# Battery_Display_Board.net
KiCad netlist of a schematic drawn in EAGLE
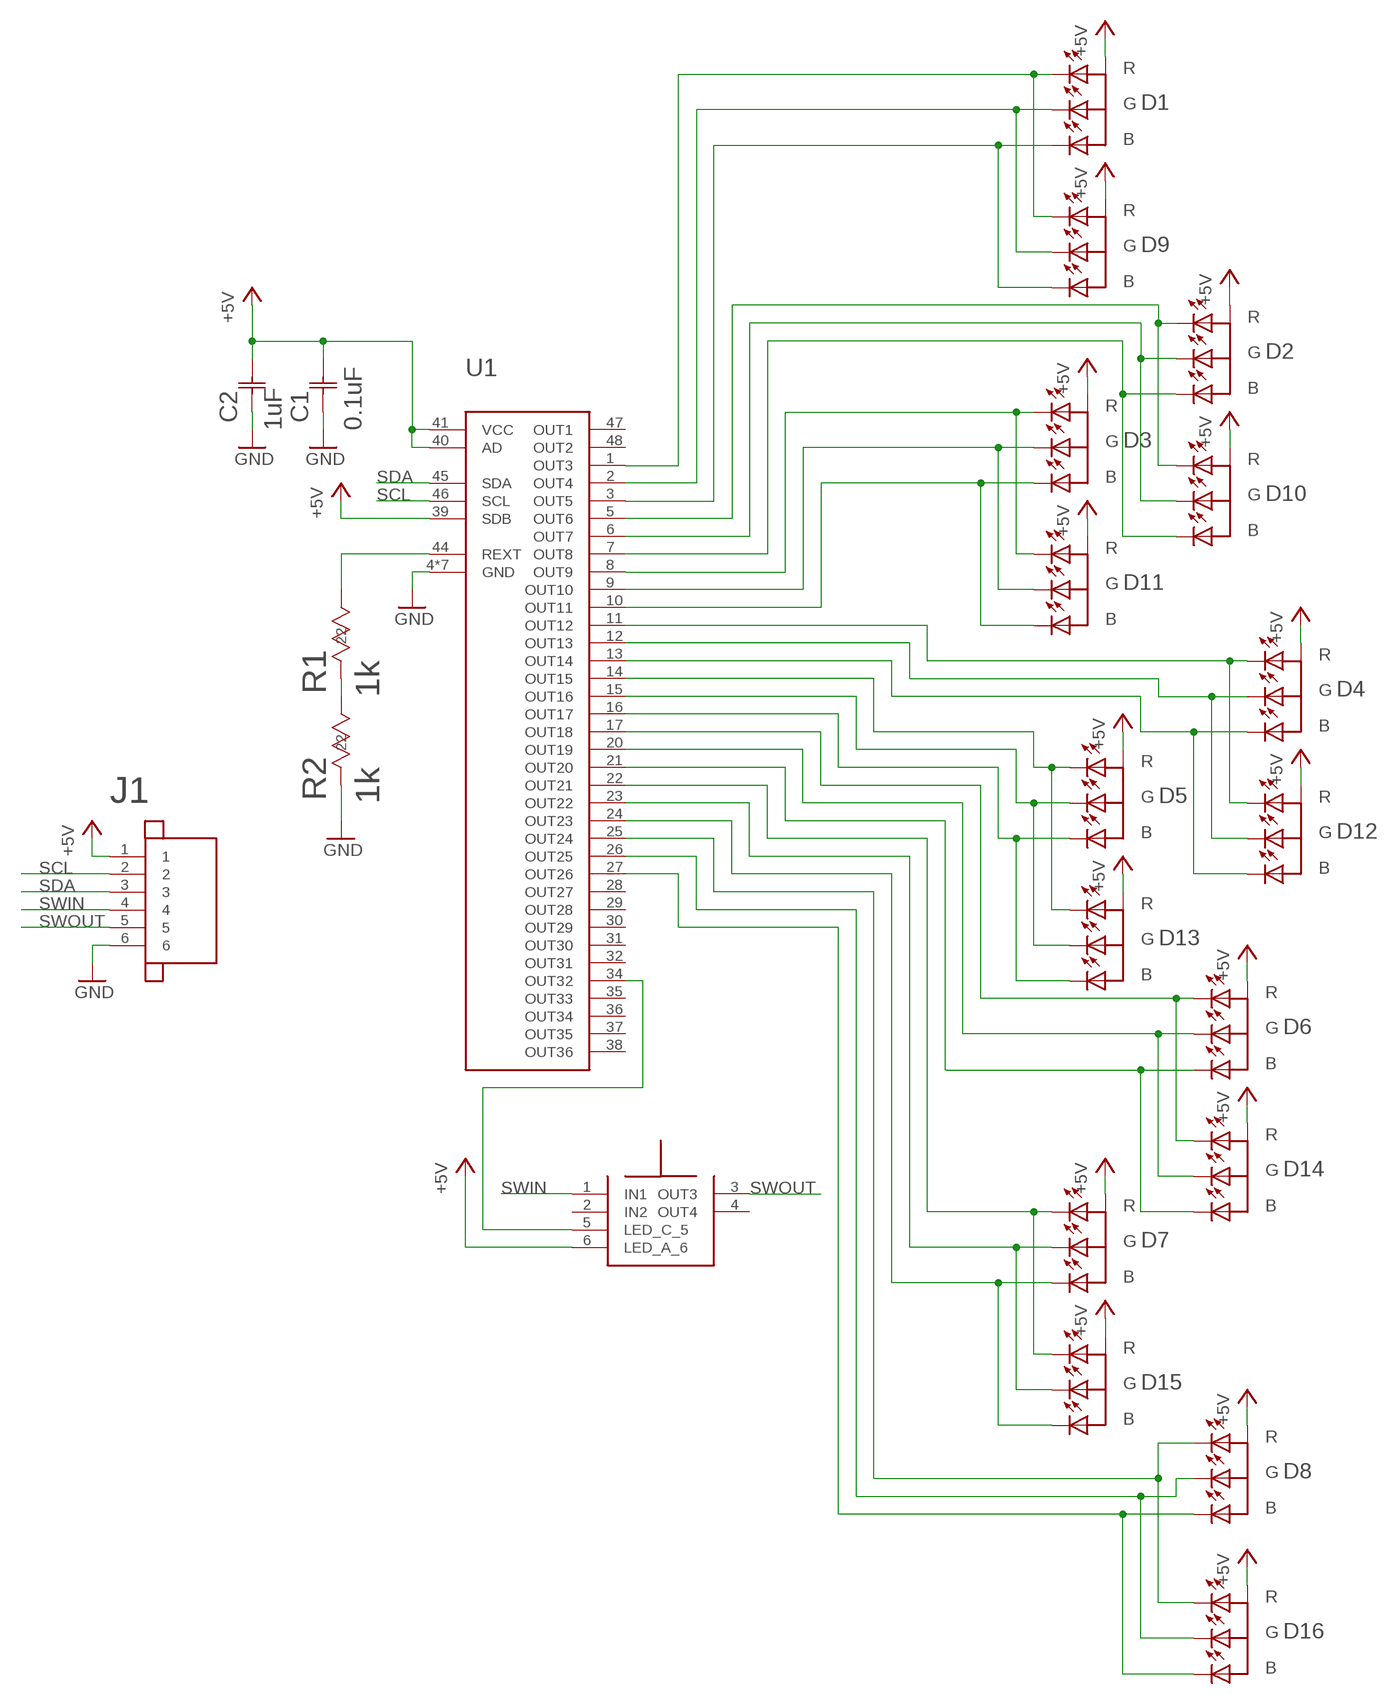
[diagram p0: schematic, sheet 1]

(export (version "E")
  (design (tool "Eeschema 10.0.6"))
  (components
    (comp (ref "C1")
      (value "0.1uF")
      (footprint "eagle-import:0805")
      (fields
        (field (name "MANUFACTURER_PART_NUMBER") "08055C104KAT2A")
        (field (name "COPYRIGHT") "Copyright C 2015 Accelerated Designs. All rights reserved")
      )
      (libsource (lib "eagle-import") (part "08055C104KAT2A"))
    )
    (comp (ref "C2")
      (value "1uF")
      (footprint "eagle-import:YAG_CC0805")
      (fields
        (field (name "MANUFACTURER_PART_NUMBER") "CC0805KKX7R7BB105")
        (field (name "COPYRIGHT") "Copyright C 2015 Accelerated Designs. All rights reserved")
      )
      (libsource (lib "eagle-import") (part "CC0805KKX7R7BB105"))
    )
    (comp (ref "D1")
      (value "ASMB-MTB0-0A3A2")
      (footprint "eagle-import:ASMB-MTB0_LED")
      (libsource (lib "eagle-import") (part "ASMB-MTB0-0A3A2"))
    )
    (comp (ref "D2")
      (value "ASMB-MTB0-0A3A2")
      (footprint "eagle-import:ASMB-MTB0_LED")
      (libsource (lib "eagle-import") (part "ASMB-MTB0-0A3A2"))
    )
    (comp (ref "D3")
      (value "ASMB-MTB0-0A3A2")
      (footprint "eagle-import:ASMB-MTB0_LED")
      (libsource (lib "eagle-import") (part "ASMB-MTB0-0A3A2"))
    )
    (comp (ref "D4")
      (value "ASMB-MTB0-0A3A2")
      (footprint "eagle-import:ASMB-MTB0_LED")
      (libsource (lib "eagle-import") (part "ASMB-MTB0-0A3A2"))
    )
    (comp (ref "D5")
      (value "ASMB-MTB0-0A3A2")
      (footprint "eagle-import:ASMB-MTB0_LED")
      (libsource (lib "eagle-import") (part "ASMB-MTB0-0A3A2"))
    )
    (comp (ref "D6")
      (value "ASMB-MTB0-0A3A2")
      (footprint "eagle-import:ASMB-MTB0_LED")
      (libsource (lib "eagle-import") (part "ASMB-MTB0-0A3A2"))
    )
    (comp (ref "D7")
      (value "ASMB-MTB0-0A3A2")
      (footprint "eagle-import:ASMB-MTB0_LED")
      (libsource (lib "eagle-import") (part "ASMB-MTB0-0A3A2"))
    )
    (comp (ref "D8")
      (value "ASMB-MTB0-0A3A2")
      (footprint "eagle-import:ASMB-MTB0_LED")
      (libsource (lib "eagle-import") (part "ASMB-MTB0-0A3A2"))
    )
    (comp (ref "D9")
      (value "ASMB-MTB0-0A3A2")
      (footprint "eagle-import:ASMB-MTB0_LED")
      (libsource (lib "eagle-import") (part "ASMB-MTB0-0A3A2"))
    )
    (comp (ref "D10")
      (value "ASMB-MTB0-0A3A2")
      (footprint "eagle-import:ASMB-MTB0_LED")
      (libsource (lib "eagle-import") (part "ASMB-MTB0-0A3A2"))
    )
    (comp (ref "D11")
      (value "ASMB-MTB0-0A3A2")
      (footprint "eagle-import:ASMB-MTB0_LED")
      (libsource (lib "eagle-import") (part "ASMB-MTB0-0A3A2"))
    )
    (comp (ref "D12")
      (value "ASMB-MTB0-0A3A2")
      (footprint "eagle-import:ASMB-MTB0_LED")
      (libsource (lib "eagle-import") (part "ASMB-MTB0-0A3A2"))
    )
    (comp (ref "D13")
      (value "ASMB-MTB0-0A3A2")
      (footprint "eagle-import:ASMB-MTB0_LED")
      (libsource (lib "eagle-import") (part "ASMB-MTB0-0A3A2"))
    )
    (comp (ref "D14")
      (value "ASMB-MTB0-0A3A2")
      (footprint "eagle-import:ASMB-MTB0_LED")
      (libsource (lib "eagle-import") (part "ASMB-MTB0-0A3A2"))
    )
    (comp (ref "D15")
      (value "ASMB-MTB0-0A3A2")
      (footprint "eagle-import:ASMB-MTB0_LED")
      (libsource (lib "eagle-import") (part "ASMB-MTB0-0A3A2"))
    )
    (comp (ref "D16")
      (value "ASMB-MTB0-0A3A2")
      (footprint "eagle-import:ASMB-MTB0_LED")
      (libsource (lib "eagle-import") (part "ASMB-MTB0-0A3A2"))
    )
    (comp (ref "J1")
      (value "JST_SH_6POS_SIDE")
      (footprint "eagle-import:JST_SH_6POS_SIDE")
      (libsource (lib "eagle-import") (part "JST_SH_6POS_SIDE"))
    )
    (comp (ref "R1")
      (value "1k")
      (footprint "eagle-import:RC0603N-M")
      (fields
        (field (name "DIGIKEYPARTNUMBER") "3111.0KGRTRND")
        (field (name "MANUFACTURER_PART_NUMBER") "RC0603JR071KL")
        (field (name "NEWARKPARTNUMBER") "14M7231")
        (field (name "COPYRIGHT") "Copyright C 2015 Accelerated Designs. All rights reserved")
      )
      (libsource (lib "eagle-import") (part "RC0603JR-071KLRC0603N-M"))
    )
    (comp (ref "R2")
      (value "1k")
      (footprint "eagle-import:RC0603N-M")
      (fields
        (field (name "DIGIKEYPARTNUMBER") "3111.0KGRTRND")
        (field (name "MANUFACTURER_PART_NUMBER") "RC0603JR071KL")
        (field (name "NEWARKPARTNUMBER") "14M7231")
        (field (name "COPYRIGHT") "Copyright C 2015 Accelerated Designs. All rights reserved")
      )
      (libsource (lib "eagle-import") (part "RC0603JR-071KLRC0603N-M"))
    )
    (comp (ref "U$2")
      (value "LED_TACT_SWITCH")
      (footprint "eagle-import:LED_TACT_SWITCH")
      (libsource (lib "eagle-import") (part "LED_TACT_SWITCH"))
    )
    (comp (ref "U1")
      (value "IS31FL3236")
      (footprint "eagle-import:TQFP-48")
      (libsource (lib "eagle-import") (part "IS31FL3236"))
    )
  )
  (nets
    (net (code "1") (name "+5V") (class "Default")
      (node (ref "C1") (pin "2") (pinfunction "2_2") (pintype "passive"))
      (node (ref "C2") (pin "2") (pinfunction "22_2") (pintype "passive"))
      (node (ref "D1") (pin "1") (pinfunction "A_1") (pintype "passive"))
      (node (ref "D10") (pin "1") (pinfunction "A_1") (pintype "passive"))
      (node (ref "D11") (pin "1") (pinfunction "A_1") (pintype "passive"))
      (node (ref "D12") (pin "1") (pinfunction "A_1") (pintype "passive"))
      (node (ref "D13") (pin "1") (pinfunction "A_1") (pintype "passive"))
      (node (ref "D14") (pin "1") (pinfunction "A_1") (pintype "passive"))
      (node (ref "D15") (pin "1") (pinfunction "A_1") (pintype "passive"))
      (node (ref "D16") (pin "1") (pinfunction "A_1") (pintype "passive"))
      (node (ref "D2") (pin "1") (pinfunction "A_1") (pintype "passive"))
      (node (ref "D3") (pin "1") (pinfunction "A_1") (pintype "passive"))
      (node (ref "D4") (pin "1") (pinfunction "A_1") (pintype "passive"))
      (node (ref "D5") (pin "1") (pinfunction "A_1") (pintype "passive"))
      (node (ref "D6") (pin "1") (pinfunction "A_1") (pintype "passive"))
      (node (ref "D7") (pin "1") (pinfunction "A_1") (pintype "passive"))
      (node (ref "D8") (pin "1") (pinfunction "A_1") (pintype "passive"))
      (node (ref "D9") (pin "1") (pinfunction "A_1") (pintype "passive"))
      (node (ref "J1") (pin "1") (pinfunction "1_1") (pintype "bidirectional"))
      (node (ref "U$2") (pin "6") (pinfunction "LED_A_6_6") (pintype "bidirectional"))
      (node (ref "U1") (pin "39") (pinfunction "SDB_39") (pintype "bidirectional"))
      (node (ref "U1") (pin "40") (pinfunction "AD_40") (pintype "bidirectional"))
      (node (ref "U1") (pin "41") (pinfunction "VCC_41") (pintype "bidirectional"))
    )
    (net (code "2") (name "/SCL") (class "Default")
      (node (ref "J1") (pin "2") (pinfunction "2_2") (pintype "bidirectional"))
      (node (ref "U1") (pin "46") (pinfunction "SCL_46") (pintype "bidirectional"))
    )
    (net (code "3") (name "/SDA") (class "Default")
      (node (ref "J1") (pin "3") (pinfunction "3_3") (pintype "bidirectional"))
      (node (ref "U1") (pin "45") (pinfunction "SDA_45") (pintype "bidirectional"))
    )
    (net (code "4") (name "/SWIN") (class "Default")
      (node (ref "J1") (pin "4") (pinfunction "4_4") (pintype "bidirectional"))
      (node (ref "U$2") (pin "1") (pinfunction "IN1_1") (pintype "bidirectional"))
    )
    (net (code "5") (name "/SWOUT") (class "Default")
      (node (ref "J1") (pin "5") (pinfunction "5_5") (pintype "bidirectional"))
      (node (ref "U$2") (pin "3") (pinfunction "OUT3_3") (pintype "bidirectional"))
    )
    (net (code "6") (name "GND") (class "Default")
      (node (ref "C1") (pin "1") (pinfunction "1_1") (pintype "passive"))
      (node (ref "C2") (pin "1") (pinfunction "11_1") (pintype "passive"))
      (node (ref "J1") (pin "6") (pinfunction "6_6") (pintype "bidirectional"))
      (node (ref "R2") (pin "2") (pinfunction "22_2") (pintype "passive"))
      (node (ref "U1") (pin "18") (pinfunction "GND_18") (pintype "bidirectional"))
      (node (ref "U1") (pin "19") (pinfunction "GND_19") (pintype "bidirectional"))
      (node (ref "U1") (pin "33") (pinfunction "GND_33") (pintype "bidirectional"))
      (node (ref "U1") (pin "4") (pinfunction "GND_4") (pintype "bidirectional"))
      (node (ref "U1") (pin "42") (pinfunction "GND_42") (pintype "bidirectional"))
      (node (ref "U1") (pin "43") (pinfunction "GND_43") (pintype "bidirectional"))
      (node (ref "U1") (pin "EP") (pinfunction "GND_EP") (pintype "bidirectional"))
    )
    (net (code "7") (name "Net-(D1-B)") (class "Default")
      (node (ref "D1") (pin "2") (pinfunction "B_2") (pintype "passive"))
      (node (ref "D9") (pin "2") (pinfunction "B_2") (pintype "passive"))
      (node (ref "U1") (pin "3") (pinfunction "OUT5_3") (pintype "bidirectional"))
    )
    (net (code "8") (name "Net-(D1-G)") (class "Default")
      (node (ref "D1") (pin "3") (pinfunction "G_3") (pintype "passive"))
      (node (ref "D9") (pin "3") (pinfunction "G_3") (pintype "passive"))
      (node (ref "U1") (pin "2") (pinfunction "OUT4_2") (pintype "bidirectional"))
    )
    (net (code "9") (name "Net-(D1-R)") (class "Default")
      (node (ref "D1") (pin "4") (pinfunction "R_4") (pintype "passive"))
      (node (ref "D9") (pin "4") (pinfunction "R_4") (pintype "passive"))
      (node (ref "U1") (pin "1") (pinfunction "OUT3_1") (pintype "bidirectional"))
    )
    (net (code "10") (name "Net-(D10-B)") (class "Default")
      (node (ref "D10") (pin "2") (pinfunction "B_2") (pintype "passive"))
      (node (ref "D2") (pin "2") (pinfunction "B_2") (pintype "passive"))
      (node (ref "U1") (pin "7") (pinfunction "OUT8_7") (pintype "bidirectional"))
    )
    (net (code "11") (name "Net-(D10-G)") (class "Default")
      (node (ref "D10") (pin "3") (pinfunction "G_3") (pintype "passive"))
      (node (ref "D2") (pin "3") (pinfunction "G_3") (pintype "passive"))
      (node (ref "U1") (pin "6") (pinfunction "OUT7_6") (pintype "bidirectional"))
    )
    (net (code "12") (name "Net-(D10-R)") (class "Default")
      (node (ref "D10") (pin "4") (pinfunction "R_4") (pintype "passive"))
      (node (ref "D2") (pin "4") (pinfunction "R_4") (pintype "passive"))
      (node (ref "U1") (pin "5") (pinfunction "OUT6_5") (pintype "bidirectional"))
    )
    (net (code "13") (name "Net-(D11-B)") (class "Default")
      (node (ref "D11") (pin "2") (pinfunction "B_2") (pintype "passive"))
      (node (ref "D3") (pin "2") (pinfunction "B_2") (pintype "passive"))
      (node (ref "U1") (pin "10") (pinfunction "OUT11_10") (pintype "bidirectional"))
    )
    (net (code "14") (name "Net-(D11-G)") (class "Default")
      (node (ref "D11") (pin "3") (pinfunction "G_3") (pintype "passive"))
      (node (ref "D3") (pin "3") (pinfunction "G_3") (pintype "passive"))
      (node (ref "U1") (pin "9") (pinfunction "OUT10_9") (pintype "bidirectional"))
    )
    (net (code "15") (name "Net-(D11-R)") (class "Default")
      (node (ref "D11") (pin "4") (pinfunction "R_4") (pintype "passive"))
      (node (ref "D3") (pin "4") (pinfunction "R_4") (pintype "passive"))
      (node (ref "U1") (pin "8") (pinfunction "OUT9_8") (pintype "bidirectional"))
    )
    (net (code "16") (name "Net-(D12-B)") (class "Default")
      (node (ref "D12") (pin "2") (pinfunction "B_2") (pintype "passive"))
      (node (ref "D4") (pin "2") (pinfunction "B_2") (pintype "passive"))
      (node (ref "U1") (pin "13") (pinfunction "OUT14_13") (pintype "bidirectional"))
    )
    (net (code "17") (name "Net-(D12-G)") (class "Default")
      (node (ref "D12") (pin "3") (pinfunction "G_3") (pintype "passive"))
      (node (ref "D4") (pin "3") (pinfunction "G_3") (pintype "passive"))
      (node (ref "U1") (pin "12") (pinfunction "OUT13_12") (pintype "bidirectional"))
    )
    (net (code "18") (name "Net-(D12-R)") (class "Default")
      (node (ref "D12") (pin "4") (pinfunction "R_4") (pintype "passive"))
      (node (ref "D4") (pin "4") (pinfunction "R_4") (pintype "passive"))
      (node (ref "U1") (pin "11") (pinfunction "OUT12_11") (pintype "bidirectional"))
    )
    (net (code "19") (name "Net-(D13-B)") (class "Default")
      (node (ref "D13") (pin "2") (pinfunction "B_2") (pintype "passive"))
      (node (ref "D5") (pin "2") (pinfunction "B_2") (pintype "passive"))
      (node (ref "U1") (pin "16") (pinfunction "OUT17_16") (pintype "bidirectional"))
    )
    (net (code "20") (name "Net-(D13-G)") (class "Default")
      (node (ref "D13") (pin "3") (pinfunction "G_3") (pintype "passive"))
      (node (ref "D5") (pin "3") (pinfunction "G_3") (pintype "passive"))
      (node (ref "U1") (pin "15") (pinfunction "OUT16_15") (pintype "bidirectional"))
    )
    (net (code "21") (name "Net-(D13-R)") (class "Default")
      (node (ref "D13") (pin "4") (pinfunction "R_4") (pintype "passive"))
      (node (ref "D5") (pin "4") (pinfunction "R_4") (pintype "passive"))
      (node (ref "U1") (pin "14") (pinfunction "OUT15_14") (pintype "bidirectional"))
    )
    (net (code "22") (name "Net-(D14-B)") (class "Default")
      (node (ref "D14") (pin "2") (pinfunction "B_2") (pintype "passive"))
      (node (ref "D6") (pin "2") (pinfunction "B_2") (pintype "passive"))
      (node (ref "U1") (pin "21") (pinfunction "OUT20_21") (pintype "bidirectional"))
    )
    (net (code "23") (name "Net-(D14-G)") (class "Default")
      (node (ref "D14") (pin "3") (pinfunction "G_3") (pintype "passive"))
      (node (ref "D6") (pin "3") (pinfunction "G_3") (pintype "passive"))
      (node (ref "U1") (pin "20") (pinfunction "OUT19_20") (pintype "bidirectional"))
    )
    (net (code "24") (name "Net-(D14-R)") (class "Default")
      (node (ref "D14") (pin "4") (pinfunction "R_4") (pintype "passive"))
      (node (ref "D6") (pin "4") (pinfunction "R_4") (pintype "passive"))
      (node (ref "U1") (pin "17") (pinfunction "OUT18_17") (pintype "bidirectional"))
    )
    (net (code "25") (name "Net-(D15-B)") (class "Default")
      (node (ref "D15") (pin "2") (pinfunction "B_2") (pintype "passive"))
      (node (ref "D7") (pin "2") (pinfunction "B_2") (pintype "passive"))
      (node (ref "U1") (pin "24") (pinfunction "OUT23_24") (pintype "bidirectional"))
    )
    (net (code "26") (name "Net-(D15-G)") (class "Default")
      (node (ref "D15") (pin "3") (pinfunction "G_3") (pintype "passive"))
      (node (ref "D7") (pin "3") (pinfunction "G_3") (pintype "passive"))
      (node (ref "U1") (pin "23") (pinfunction "OUT22_23") (pintype "bidirectional"))
    )
    (net (code "27") (name "Net-(D15-R)") (class "Default")
      (node (ref "D15") (pin "4") (pinfunction "R_4") (pintype "passive"))
      (node (ref "D7") (pin "4") (pinfunction "R_4") (pintype "passive"))
      (node (ref "U1") (pin "22") (pinfunction "OUT21_22") (pintype "bidirectional"))
    )
    (net (code "28") (name "Net-(D16-B)") (class "Default")
      (node (ref "D16") (pin "2") (pinfunction "B_2") (pintype "passive"))
      (node (ref "D8") (pin "2") (pinfunction "B_2") (pintype "passive"))
      (node (ref "U1") (pin "27") (pinfunction "OUT26_27") (pintype "bidirectional"))
    )
    (net (code "29") (name "Net-(D16-G)") (class "Default")
      (node (ref "D16") (pin "3") (pinfunction "G_3") (pintype "passive"))
      (node (ref "D8") (pin "3") (pinfunction "G_3") (pintype "passive"))
      (node (ref "U1") (pin "26") (pinfunction "OUT25_26") (pintype "bidirectional"))
    )
    (net (code "30") (name "Net-(D16-R)") (class "Default")
      (node (ref "D16") (pin "4") (pinfunction "R_4") (pintype "passive"))
      (node (ref "D8") (pin "4") (pinfunction "R_4") (pintype "passive"))
      (node (ref "U1") (pin "25") (pinfunction "OUT24_25") (pintype "bidirectional"))
    )
    (net (code "31") (name "Net-(R1-11)") (class "Default")
      (node (ref "R1") (pin "1") (pinfunction "11_1") (pintype "passive"))
      (node (ref "U1") (pin "44") (pinfunction "REXT_44") (pintype "bidirectional"))
    )
    (net (code "32") (name "Net-(R1-22)") (class "Default")
      (node (ref "R1") (pin "2") (pinfunction "22_2") (pintype "passive"))
      (node (ref "R2") (pin "1") (pinfunction "11_1") (pintype "passive"))
    )
    (net (code "33") (name "Net-(U$2-LED_C_5)") (class "Default")
      (node (ref "U$2") (pin "5") (pinfunction "LED_C_5_5") (pintype "bidirectional"))
      (node (ref "U1") (pin "34") (pinfunction "OUT32_34") (pintype "bidirectional"))
    )
    (net (code "34") (name "unconnected-(U$2-IN2-Pad2)") (class "Default")
      (node (ref "U$2") (pin "2") (pinfunction "IN2_2") (pintype "bidirectional"))
    )
    (net (code "35") (name "unconnected-(U$2-OUT4-Pad4)") (class "Default")
      (node (ref "U$2") (pin "4") (pinfunction "OUT4_4") (pintype "bidirectional"))
    )
    (net (code "36") (name "unconnected-(U1-OUT1-Pad47)") (class "Default")
      (node (ref "U1") (pin "47") (pinfunction "OUT1_47") (pintype "bidirectional"))
    )
    (net (code "37") (name "unconnected-(U1-OUT2-Pad48)") (class "Default")
      (node (ref "U1") (pin "48") (pinfunction "OUT2_48") (pintype "bidirectional"))
    )
    (net (code "38") (name "unconnected-(U1-OUT27-Pad28)") (class "Default")
      (node (ref "U1") (pin "28") (pinfunction "OUT27_28") (pintype "bidirectional"))
    )
    (net (code "39") (name "unconnected-(U1-OUT28-Pad29)") (class "Default")
      (node (ref "U1") (pin "29") (pinfunction "OUT28_29") (pintype "bidirectional"))
    )
    (net (code "40") (name "unconnected-(U1-OUT29-Pad30)") (class "Default")
      (node (ref "U1") (pin "30") (pinfunction "OUT29_30") (pintype "bidirectional"))
    )
    (net (code "41") (name "unconnected-(U1-OUT30-Pad31)") (class "Default")
      (node (ref "U1") (pin "31") (pinfunction "OUT30_31") (pintype "bidirectional"))
    )
    (net (code "42") (name "unconnected-(U1-OUT31-Pad32)") (class "Default")
      (node (ref "U1") (pin "32") (pinfunction "OUT31_32") (pintype "bidirectional"))
    )
    (net (code "43") (name "unconnected-(U1-OUT33-Pad35)") (class "Default")
      (node (ref "U1") (pin "35") (pinfunction "OUT33_35") (pintype "bidirectional"))
    )
    (net (code "44") (name "unconnected-(U1-OUT34-Pad36)") (class "Default")
      (node (ref "U1") (pin "36") (pinfunction "OUT34_36") (pintype "bidirectional"))
    )
    (net (code "45") (name "unconnected-(U1-OUT35-Pad37)") (class "Default")
      (node (ref "U1") (pin "37") (pinfunction "OUT35_37") (pintype "bidirectional"))
    )
    (net (code "46") (name "unconnected-(U1-OUT36-Pad38)") (class "Default")
      (node (ref "U1") (pin "38") (pinfunction "OUT36_38") (pintype "bidirectional"))
    )
  )
)
